# adapter-board-controller.net
KiCad netlist of a schematic drawn in EAGLE
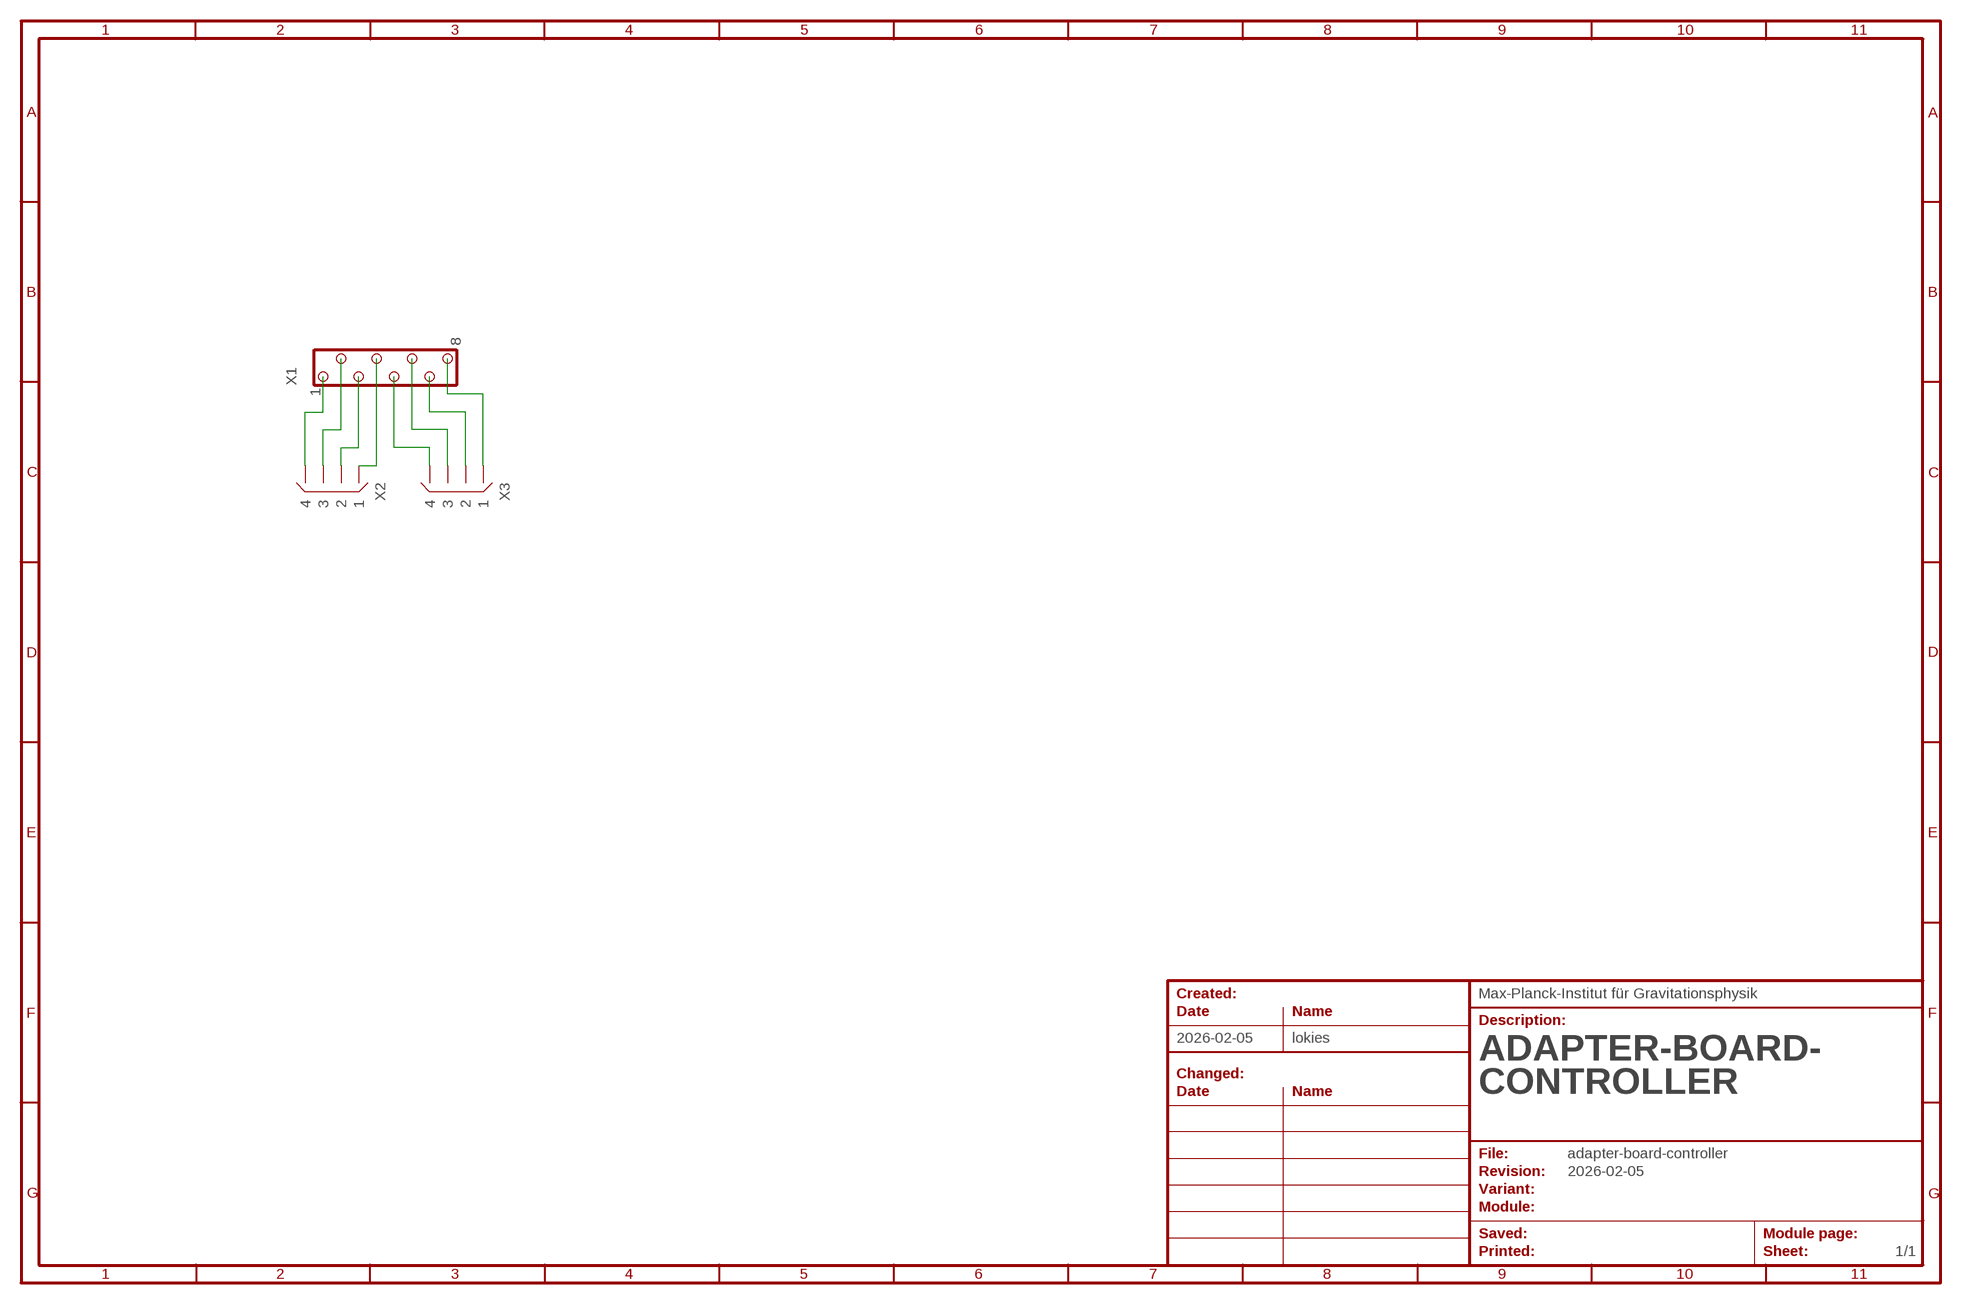
[diagram p0: schematic, sheet 1]

(export (version "E")
  (design (tool "Eeschema 10.0.6"))
  (components
    (comp (ref "X1")
      (value "XS08-RJ45")
      (footprint "eagle-import:XS08-2S-RJ45")
      (libsource (lib "eagle-import") (part "XS08-RJ45"))
    )
    (comp (ref "X2")
      (value "X04")
      (footprint "eagle-import:X04-SIL-MALE-VERT-L")
      (libsource (lib "eagle-import") (part "X04"))
    )
    (comp (ref "X3")
      (value "X04")
      (footprint "eagle-import:X04-SIL-MALE-VERT-L")
      (libsource (lib "eagle-import") (part "X04"))
    )
  )
  (nets
    (net (code "1") (name "Net-(X1-Pad1)") (class "Default")
      (node (ref "X1") (pin "1") (pinfunction "1_1") (pintype "bidirectional"))
      (node (ref "X2") (pin "4") (pinfunction "4_4") (pintype "bidirectional"))
    )
    (net (code "2") (name "Net-(X1-Pad2)") (class "Default")
      (node (ref "X1") (pin "2") (pinfunction "2_2") (pintype "bidirectional"))
      (node (ref "X2") (pin "3") (pinfunction "3_3") (pintype "bidirectional"))
    )
    (net (code "3") (name "Net-(X1-Pad3)") (class "Default")
      (node (ref "X1") (pin "3") (pinfunction "3_3") (pintype "bidirectional"))
      (node (ref "X2") (pin "2") (pinfunction "2_2") (pintype "bidirectional"))
    )
    (net (code "4") (name "Net-(X1-Pad4)") (class "Default")
      (node (ref "X1") (pin "4") (pinfunction "4_4") (pintype "bidirectional"))
      (node (ref "X2") (pin "1") (pinfunction "1_1") (pintype "bidirectional"))
    )
    (net (code "5") (name "Net-(X1-Pad5)") (class "Default")
      (node (ref "X1") (pin "5") (pinfunction "5_5") (pintype "bidirectional"))
      (node (ref "X3") (pin "4") (pinfunction "4_4") (pintype "bidirectional"))
    )
    (net (code "6") (name "Net-(X1-Pad6)") (class "Default")
      (node (ref "X1") (pin "6") (pinfunction "6_6") (pintype "bidirectional"))
      (node (ref "X3") (pin "3") (pinfunction "3_3") (pintype "bidirectional"))
    )
    (net (code "7") (name "Net-(X1-Pad7)") (class "Default")
      (node (ref "X1") (pin "7") (pinfunction "7_7") (pintype "bidirectional"))
      (node (ref "X3") (pin "2") (pinfunction "2_2") (pintype "bidirectional"))
    )
    (net (code "8") (name "Net-(X1-Pad8)") (class "Default")
      (node (ref "X1") (pin "8") (pinfunction "8_8") (pintype "bidirectional"))
      (node (ref "X3") (pin "1") (pinfunction "1_1") (pintype "bidirectional"))
    )
  )
)
